# tractor_v2.net
KiCad netlist of a schematic drawn in EAGLE
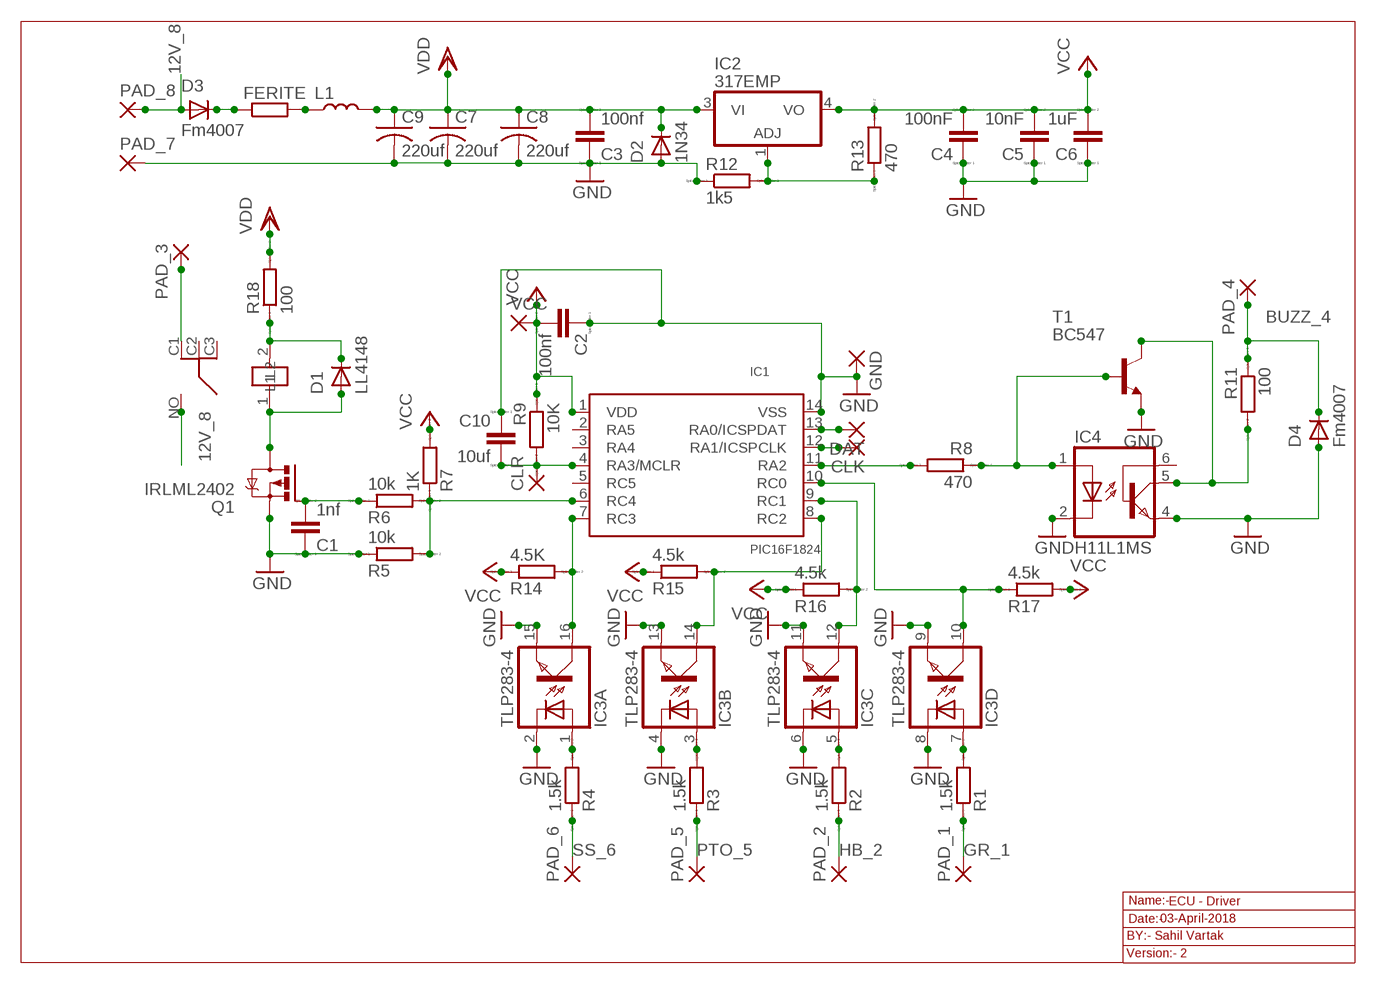
[diagram p0: schematic, sheet 1]

(export (version "E")
  (design (tool "Eeschema 10.0.6"))
  (components
    (comp (ref "C1")
      (value "1nf")
      (footprint "eagle-import:C0603")
      (libsource (lib "eagle-import") (part "CC0603"))
    )
    (comp (ref "C2")
      (value "100nf")
      (footprint "eagle-import:C0603")
      (libsource (lib "eagle-import") (part "CC0603"))
    )
    (comp (ref "C3")
      (value "100nf")
      (footprint "eagle-import:C0603")
      (libsource (lib "eagle-import") (part "CC0603"))
    )
    (comp (ref "C4")
      (value "100nF")
      (footprint "eagle-import:C0603")
      (libsource (lib "eagle-import") (part "CC0603"))
    )
    (comp (ref "C5")
      (value "10nF")
      (footprint "eagle-import:C0603")
      (libsource (lib "eagle-import") (part "CC0603"))
    )
    (comp (ref "C6")
      (value "1uF")
      (footprint "eagle-import:C0603")
      (libsource (lib "eagle-import") (part "CC0603"))
    )
    (comp (ref "C7")
      (value "220uf")
      (footprint "eagle-import:C025-025X050")
      (libsource (lib "eagle-import") (part "C-US025-025X050"))
    )
    (comp (ref "C8")
      (value "220uf")
      (footprint "eagle-import:C025-025X050")
      (libsource (lib "eagle-import") (part "C-US025-025X050"))
    )
    (comp (ref "C9")
      (value "220uf")
      (footprint "eagle-import:C025-025X050")
      (libsource (lib "eagle-import") (part "C-US025-025X050"))
    )
    (comp (ref "C10")
      (value "10uf")
      (footprint "eagle-import:C0603")
      (libsource (lib "eagle-import") (part "CC0603"))
    )
    (comp (ref "CLK")
      (value "1,6/0,8")
      (footprint "eagle-import:1,6_0,8")
      (libsource (lib "eagle-import") (part "1,6/0,8"))
    )
    (comp (ref "CLR")
      (value "1,6/0,8")
      (footprint "eagle-import:1,6_0,8")
      (libsource (lib "eagle-import") (part "1,6/0,8"))
    )
    (comp (ref "D1")
      (value "LL4148")
      (footprint "eagle-import:SMA-DO214AC")
      (libsource (lib "eagle-import") (part "GF1"))
    )
    (comp (ref "D2")
      (value "1N34")
      (footprint "eagle-import:SMA-DO214AC")
      (libsource (lib "eagle-import") (part "GF1"))
    )
    (comp (ref "D3")
      (value "Fm4007")
      (footprint "eagle-import:SMA-DO214AC")
      (libsource (lib "eagle-import") (part "GF1"))
    )
    (comp (ref "D4")
      (value "Fm4007")
      (footprint "eagle-import:SMA-DO214AC")
      (libsource (lib "eagle-import") (part "GF1"))
    )
    (comp (ref "DAT")
      (value "1,6/0,8")
      (footprint "eagle-import:1,6_0,8")
      (libsource (lib "eagle-import") (part "1,6/0,8"))
    )
    (comp (ref "FERITE")
      (value "R-EU_R0603")
      (footprint "eagle-import:R0603")
      (libsource (lib "eagle-import") (part "R-EU_R0603"))
    )
    (comp (ref "GND")
      (value "1,6/0,8")
      (footprint "eagle-import:1,6_0,8")
      (libsource (lib "eagle-import") (part "1,6/0,8"))
    )
    (comp (ref "IC1")
      (value "PIC16F1824")
      (footprint "eagle-import:SO-14")
      (libsource (lib "eagle-import") (part "PIC16F1824"))
    )
    (comp (ref "IC2")
      (value "317EMP")
      (footprint "eagle-import:SOT223")
      (libsource (lib "eagle-import") (part "317EMP"))
    )
    (comp (ref "IC3")
      (value "TLP283-4")
      (footprint "eagle-import:MINI-FLAT-16")
      (libsource (lib "eagle-import") (part "TLP283-4"))
    )
    (comp (ref "IC4")
      (value "H11L1MS")
      (footprint "eagle-import:DIL6-SMD")
      (libsource (lib "eagle-import") (part "H11LMS1"))
    )
    (comp (ref "K2")
      (value "RL703")
      (footprint "eagle-import:RL703")
      (libsource (lib "eagle-import") (part "RL703"))
    )
    (comp (ref "L1")
      (value "R-US_WSC2515")
      (footprint "eagle-import:WSC2515")
      (libsource (lib "eagle-import") (part "R-US_WSC2515"))
    )
    (comp (ref "PAD_1")
      (value "2,54/1,1")
      (footprint "eagle-import:2,54_1,1")
      (libsource (lib "eagle-import") (part "2,54/1,1"))
    )
    (comp (ref "PAD_2")
      (value "2,54/1,1")
      (footprint "eagle-import:2,54_1,1")
      (libsource (lib "eagle-import") (part "2,54/1,1"))
    )
    (comp (ref "PAD_3")
      (value "2,54/1,1")
      (footprint "eagle-import:2,54_1,1")
      (libsource (lib "eagle-import") (part "2,54/1,1"))
    )
    (comp (ref "PAD_4")
      (value "2,54/1,1")
      (footprint "eagle-import:2,54_1,1")
      (libsource (lib "eagle-import") (part "2,54/1,1"))
    )
    (comp (ref "PAD_5")
      (value "2,54/1,1")
      (footprint "eagle-import:2,54_1,1")
      (libsource (lib "eagle-import") (part "2,54/1,1"))
    )
    (comp (ref "PAD_6")
      (value "2,54/1,1")
      (footprint "eagle-import:2,54_1,1")
      (libsource (lib "eagle-import") (part "2,54/1,1"))
    )
    (comp (ref "PAD_7")
      (value "2,54/1,1")
      (footprint "eagle-import:2,54_1,1")
      (libsource (lib "eagle-import") (part "2,54/1,1"))
    )
    (comp (ref "PAD_8")
      (value "2,54/1,1")
      (footprint "eagle-import:2,54_1,1")
      (libsource (lib "eagle-import") (part "2,54/1,1"))
    )
    (comp (ref "Q1")
      (value "IRLML2402")
      (footprint "eagle-import:MICRO3")
      (libsource (lib "eagle-import") (part "IRLML5203"))
    )
    (comp (ref "R1")
      (value "1.5k")
      (footprint "eagle-import:R0603")
      (libsource (lib "eagle-import") (part "RR0603"))
    )
    (comp (ref "R2")
      (value "1.5k")
      (footprint "eagle-import:R0603")
      (libsource (lib "eagle-import") (part "RR0603"))
    )
    (comp (ref "R3")
      (value "1.5k")
      (footprint "eagle-import:R0603")
      (libsource (lib "eagle-import") (part "RR0603"))
    )
    (comp (ref "R4")
      (value "1.5k")
      (footprint "eagle-import:R0603")
      (libsource (lib "eagle-import") (part "RR0603"))
    )
    (comp (ref "R5")
      (value "10k")
      (footprint "eagle-import:R0603")
      (libsource (lib "eagle-import") (part "RR0603"))
    )
    (comp (ref "R6")
      (value "10k")
      (footprint "eagle-import:R0603")
      (libsource (lib "eagle-import") (part "RR0603"))
    )
    (comp (ref "R7")
      (value "1K")
      (footprint "eagle-import:R0603")
      (libsource (lib "eagle-import") (part "RR0603"))
    )
    (comp (ref "R8")
      (value "470")
      (footprint "eagle-import:R0603")
      (libsource (lib "eagle-import") (part "RR0603"))
    )
    (comp (ref "R9")
      (value "10K")
      (footprint "eagle-import:R0603")
      (libsource (lib "eagle-import") (part "RR0603"))
    )
    (comp (ref "R11")
      (value "100")
      (footprint "eagle-import:R0603")
      (libsource (lib "eagle-import") (part "RR0603"))
    )
    (comp (ref "R12")
      (value "1k5")
      (footprint "eagle-import:R0603")
      (libsource (lib "eagle-import") (part "RR0603"))
    )
    (comp (ref "R13")
      (value "470")
      (footprint "eagle-import:R0603")
      (libsource (lib "eagle-import") (part "RR0603"))
    )
    (comp (ref "R14")
      (value "4.5K")
      (footprint "eagle-import:R0603")
      (libsource (lib "eagle-import") (part "RR0603"))
    )
    (comp (ref "R15")
      (value "4.5k")
      (footprint "eagle-import:R0603")
      (libsource (lib "eagle-import") (part "RR0603"))
    )
    (comp (ref "R16")
      (value "4.5k")
      (footprint "eagle-import:R0603")
      (libsource (lib "eagle-import") (part "RR0603"))
    )
    (comp (ref "R17")
      (value "4.5k")
      (footprint "eagle-import:R0603")
      (libsource (lib "eagle-import") (part "RR0603"))
    )
    (comp (ref "R18")
      (value "100")
      (footprint "eagle-import:R0603")
      (libsource (lib "eagle-import") (part "RR0603"))
    )
    (comp (ref "T1")
      (value "BC547")
      (footprint "eagle-import:TO92")
      (libsource (lib "eagle-import") (part "BC547"))
    )
    (comp (ref "VCC")
      (value "1,6/0,8")
      (footprint "eagle-import:1,6_0,8")
      (libsource (lib "eagle-import") (part "1,6/0,8"))
    )
  )
  (nets
    (net (code "1") (name "/12V_8") (class "Default")
      (node (ref "D3") (pin "A") (pinfunction "A_A") (pintype "passive"))
      (node (ref "K2") (pin "NO") (pinfunction "NO_NO") (pintype "bidirectional"))
      (node (ref "PAD_8") (pin "1") (pinfunction "P_1") (pintype "passive"))
    )
    (net (code "2") (name "/BUZZ_4") (class "Default")
      (node (ref "D4") (pin "K") (pinfunction "C_K") (pintype "passive"))
      (node (ref "PAD_4") (pin "1") (pinfunction "P_1") (pintype "passive"))
      (node (ref "R11") (pin "1") (pinfunction "1_1") (pintype "passive"))
    )
    (net (code "3") (name "/GR_1") (class "Default")
      (node (ref "PAD_1") (pin "1") (pinfunction "P_1") (pintype "passive"))
      (node (ref "R1") (pin "1") (pinfunction "1_1") (pintype "passive"))
    )
    (net (code "4") (name "/HB_2") (class "Default")
      (node (ref "PAD_2") (pin "1") (pinfunction "P_1") (pintype "passive"))
      (node (ref "R2") (pin "1") (pinfunction "1_1") (pintype "passive"))
    )
    (net (code "5") (name "/PTO_5") (class "Default")
      (node (ref "PAD_5") (pin "1") (pinfunction "P_1") (pintype "passive"))
      (node (ref "R3") (pin "1") (pinfunction "1_1") (pintype "passive"))
    )
    (net (code "6") (name "/SS_6") (class "Default")
      (node (ref "PAD_6") (pin "1") (pinfunction "P_1") (pintype "passive"))
      (node (ref "R4") (pin "1") (pinfunction "1_1") (pintype "passive"))
    )
    (net (code "7") (name "GND") (class "Default")
      (node (ref "C1") (pin "1") (pinfunction "1_1") (pintype "passive"))
      (node (ref "C10") (pin "1") (pinfunction "1_1") (pintype "passive"))
      (node (ref "C2") (pin "1") (pinfunction "1_1") (pintype "passive"))
      (node (ref "C3") (pin "1") (pinfunction "1_1") (pintype "passive"))
      (node (ref "C4") (pin "1") (pinfunction "1_1") (pintype "passive"))
      (node (ref "C5") (pin "1") (pinfunction "1_1") (pintype "passive"))
      (node (ref "C6") (pin "1") (pinfunction "1_1") (pintype "passive"))
      (node (ref "C7") (pin "2") (pinfunction "2_2") (pintype "passive"))
      (node (ref "C8") (pin "2") (pinfunction "2_2") (pintype "passive"))
      (node (ref "C9") (pin "2") (pinfunction "2_2") (pintype "passive"))
      (node (ref "D2") (pin "A") (pinfunction "A_A") (pintype "passive"))
      (node (ref "D4") (pin "A") (pinfunction "A_A") (pintype "passive"))
      (node (ref "GND") (pin "1") (pinfunction "P_1") (pintype "passive"))
      (node (ref "IC1") (pin "14") (pinfunction "VSS_14") (pintype "bidirectional"))
      (node (ref "IC3") (pin "11") (pinfunction "EMIT_11") (pintype "passive"))
      (node (ref "IC3") (pin "13") (pinfunction "EMIT_13") (pintype "passive"))
      (node (ref "IC3") (pin "15") (pinfunction "EMIT_15") (pintype "passive"))
      (node (ref "IC3") (pin "2") (pinfunction "C_2") (pintype "passive"))
      (node (ref "IC3") (pin "4") (pinfunction "C_4") (pintype "passive"))
      (node (ref "IC3") (pin "6") (pinfunction "C_6") (pintype "passive"))
      (node (ref "IC3") (pin "8") (pinfunction "C_8") (pintype "passive"))
      (node (ref "IC3") (pin "9") (pinfunction "EMIT_9") (pintype "passive"))
      (node (ref "IC4") (pin "2") (pinfunction "C_2") (pintype "passive"))
      (node (ref "IC4") (pin "4") (pinfunction "EMI_4") (pintype "passive"))
      (node (ref "PAD_7") (pin "1") (pinfunction "P_1") (pintype "passive"))
      (node (ref "Q1") (pin "2") (pinfunction "S_2") (pintype "passive"))
      (node (ref "R12") (pin "1") (pinfunction "1_1") (pintype "passive"))
      (node (ref "R5") (pin "1") (pinfunction "1_1") (pintype "passive"))
      (node (ref "T1") (pin "1") (pinfunction "E_1") (pintype "passive"))
    )
    (net (code "8") (name "Net-(CLK-P)") (class "Default")
      (node (ref "CLK") (pin "1") (pinfunction "P_1") (pintype "passive"))
      (node (ref "IC1") (pin "12") (pinfunction "RA1/ICSPCLK_12") (pintype "bidirectional"))
    )
    (net (code "9") (name "Net-(CLR-P)") (class "Default")
      (node (ref "C10") (pin "2") (pinfunction "2_2") (pintype "passive"))
      (node (ref "CLR") (pin "1") (pinfunction "P_1") (pintype "passive"))
      (node (ref "IC1") (pin "4") (pinfunction "RA3/MCLR_4") (pintype "bidirectional"))
      (node (ref "R9") (pin "2") (pinfunction "2_2") (pintype "passive"))
    )
    (net (code "10") (name "Net-(D1-C)") (class "Default")
      (node (ref "D1") (pin "K") (pinfunction "C_K") (pintype "passive"))
      (node (ref "K2") (pin "2") (pinfunction "L1_2") (pintype "bidirectional"))
      (node (ref "R18") (pin "1") (pinfunction "1_1") (pintype "passive"))
    )
    (net (code "11") (name "Net-(D3-C)") (class "Default")
      (node (ref "D3") (pin "K") (pinfunction "C_K") (pintype "passive"))
      (node (ref "FERITE") (pin "1") (pinfunction "1_1") (pintype "passive"))
    )
    (net (code "12") (name "Net-(DAT-P)") (class "Default")
      (node (ref "DAT") (pin "1") (pinfunction "P_1") (pintype "passive"))
      (node (ref "IC1") (pin "13") (pinfunction "RA0/ICSPDAT_13") (pintype "bidirectional"))
    )
    (net (code "13") (name "Net-(FERITE-Pad2)") (class "Default")
      (node (ref "FERITE") (pin "2") (pinfunction "2_2") (pintype "passive"))
      (node (ref "L1") (pin "1") (pinfunction "1_1") (pintype "passive"))
    )
    (net (code "14") (name "Net-(IC1-RA2)") (class "Default")
      (node (ref "IC1") (pin "11") (pinfunction "RA2_11") (pintype "bidirectional"))
      (node (ref "R8") (pin "2") (pinfunction "2_2") (pintype "passive"))
    )
    (net (code "15") (name "Net-(IC1-RC0)") (class "Default")
      (node (ref "IC1") (pin "10") (pinfunction "RC0_10") (pintype "bidirectional"))
      (node (ref "IC3") (pin "10") (pinfunction "COL_10") (pintype "passive"))
      (node (ref "R17") (pin "1") (pinfunction "1_1") (pintype "passive"))
    )
    (net (code "16") (name "Net-(IC1-RC1)") (class "Default")
      (node (ref "IC1") (pin "9") (pinfunction "RC1_9") (pintype "bidirectional"))
      (node (ref "IC3") (pin "12") (pinfunction "COL_12") (pintype "passive"))
      (node (ref "R16") (pin "2") (pinfunction "2_2") (pintype "passive"))
    )
    (net (code "17") (name "Net-(IC1-RC2)") (class "Default")
      (node (ref "IC1") (pin "8") (pinfunction "RC2_8") (pintype "bidirectional"))
      (node (ref "IC3") (pin "14") (pinfunction "COL_14") (pintype "passive"))
      (node (ref "R15") (pin "2") (pinfunction "2_2") (pintype "passive"))
    )
    (net (code "18") (name "Net-(IC1-RC3)") (class "Default")
      (node (ref "IC1") (pin "7") (pinfunction "RC3_7") (pintype "bidirectional"))
      (node (ref "IC3") (pin "16") (pinfunction "COL_16") (pintype "passive"))
      (node (ref "R14") (pin "2") (pinfunction "2_2") (pintype "passive"))
    )
    (net (code "19") (name "Net-(IC1-RC4)") (class "Default")
      (node (ref "IC1") (pin "6") (pinfunction "RC4_6") (pintype "bidirectional"))
      (node (ref "R5") (pin "2") (pinfunction "2_2") (pintype "passive"))
      (node (ref "R6") (pin "2") (pinfunction "2_2") (pintype "passive"))
      (node (ref "R7") (pin "1") (pinfunction "1_1") (pintype "passive"))
    )
    (net (code "20") (name "Net-(IC2-ADJ)") (class "Default")
      (node (ref "IC2") (pin "1") (pinfunction "ADJ_1") (pintype "input"))
      (node (ref "R12") (pin "2") (pinfunction "2_2") (pintype "passive"))
      (node (ref "R13") (pin "1") (pinfunction "1_1") (pintype "passive"))
    )
    (net (code "21") (name "Net-(IC3A-A)") (class "Default")
      (node (ref "IC3") (pin "1") (pinfunction "A_1") (pintype "passive"))
      (node (ref "R4") (pin "2") (pinfunction "2_2") (pintype "passive"))
    )
    (net (code "22") (name "Net-(IC3B-A)") (class "Default")
      (node (ref "IC3") (pin "3") (pinfunction "A_3") (pintype "passive"))
      (node (ref "R3") (pin "2") (pinfunction "2_2") (pintype "passive"))
    )
    (net (code "23") (name "Net-(IC3C-A)") (class "Default")
      (node (ref "IC3") (pin "5") (pinfunction "A_5") (pintype "passive"))
      (node (ref "R2") (pin "2") (pinfunction "2_2") (pintype "passive"))
    )
    (net (code "24") (name "Net-(IC3D-A)") (class "Default")
      (node (ref "IC3") (pin "7") (pinfunction "A_7") (pintype "passive"))
      (node (ref "R1") (pin "2") (pinfunction "2_2") (pintype "passive"))
    )
    (net (code "25") (name "Net-(IC4-A)") (class "Default")
      (node (ref "IC4") (pin "1") (pinfunction "A_1") (pintype "passive"))
      (node (ref "R8") (pin "1") (pinfunction "1_1") (pintype "passive"))
      (node (ref "T1") (pin "2") (pinfunction "B_2") (pintype "passive"))
    )
    (net (code "26") (name "Net-(IC4-COL)") (class "Default")
      (node (ref "IC4") (pin "5") (pinfunction "COL_5") (pintype "passive"))
      (node (ref "R11") (pin "2") (pinfunction "2_2") (pintype "passive"))
      (node (ref "T1") (pin "3") (pinfunction "C_3") (pintype "passive"))
    )
    (net (code "27") (name "Net-(K2-L2)") (class "Default")
      (node (ref "D1") (pin "A") (pinfunction "A_A") (pintype "passive"))
      (node (ref "K2") (pin "1") (pinfunction "L2_1") (pintype "bidirectional"))
      (node (ref "Q1") (pin "3") (pinfunction "D_3") (pintype "passive"))
    )
    (net (code "28") (name "Net-(PAD_3-P)") (class "Default")
      (node (ref "K2") (pin "C1") (pinfunction "C1_C1") (pintype "bidirectional"))
      (node (ref "PAD_3") (pin "1") (pinfunction "P_1") (pintype "passive"))
    )
    (net (code "29") (name "Net-(Q1-G)") (class "Default")
      (node (ref "C1") (pin "2") (pinfunction "2_2") (pintype "passive"))
      (node (ref "Q1") (pin "1") (pinfunction "G_1") (pintype "passive"))
      (node (ref "R6") (pin "1") (pinfunction "1_1") (pintype "passive"))
    )
    (net (code "30") (name "VCC") (class "Default")
      (node (ref "C2") (pin "2") (pinfunction "2_2") (pintype "passive"))
      (node (ref "C4") (pin "2") (pinfunction "2_2") (pintype "passive"))
      (node (ref "C5") (pin "2") (pinfunction "2_2") (pintype "passive"))
      (node (ref "C6") (pin "2") (pinfunction "2_2") (pintype "passive"))
      (node (ref "IC1") (pin "1") (pinfunction "VDD_1") (pintype "bidirectional"))
      (node (ref "IC2") (pin "4") (pinfunction "VO_4") (pintype "passive"))
      (node (ref "R13") (pin "2") (pinfunction "2_2") (pintype "passive"))
      (node (ref "R14") (pin "1") (pinfunction "1_1") (pintype "passive"))
      (node (ref "R15") (pin "1") (pinfunction "1_1") (pintype "passive"))
      (node (ref "R16") (pin "1") (pinfunction "1_1") (pintype "passive"))
      (node (ref "R17") (pin "2") (pinfunction "2_2") (pintype "passive"))
      (node (ref "R7") (pin "2") (pinfunction "2_2") (pintype "passive"))
      (node (ref "R9") (pin "1") (pinfunction "1_1") (pintype "passive"))
      (node (ref "VCC") (pin "1") (pinfunction "P_1") (pintype "passive"))
    )
    (net (code "31") (name "VDD") (class "Default")
      (node (ref "C3") (pin "2") (pinfunction "2_2") (pintype "passive"))
      (node (ref "C7") (pin "1") (pinfunction "1_1") (pintype "passive"))
      (node (ref "C8") (pin "1") (pinfunction "1_1") (pintype "passive"))
      (node (ref "C9") (pin "1") (pinfunction "1_1") (pintype "passive"))
      (node (ref "D2") (pin "K") (pinfunction "C_K") (pintype "passive"))
      (node (ref "IC2") (pin "3") (pinfunction "VI_3") (pintype "input"))
      (node (ref "L1") (pin "2") (pinfunction "2_2") (pintype "passive"))
      (node (ref "R18") (pin "2") (pinfunction "2_2") (pintype "passive"))
    )
    (net (code "32") (name "unconnected-(IC1-RA4-Pad3)") (class "Default")
      (node (ref "IC1") (pin "3") (pinfunction "RA4_3") (pintype "bidirectional"))
    )
    (net (code "33") (name "unconnected-(IC1-RA5-Pad2)") (class "Default")
      (node (ref "IC1") (pin "2") (pinfunction "RA5_2") (pintype "bidirectional"))
    )
    (net (code "34") (name "unconnected-(IC1-RC5-Pad5)") (class "Default")
      (node (ref "IC1") (pin "5") (pinfunction "RC5_5") (pintype "bidirectional"))
    )
    (net (code "35") (name "unconnected-(IC4-BAS-Pad6)") (class "Default")
      (node (ref "IC4") (pin "6") (pinfunction "BAS_6") (pintype "passive"))
    )
    (net (code "36") (name "unconnected-(K2-PadC2)") (class "Default")
      (node (ref "K2") (pin "C2") (pinfunction "C2_C2") (pintype "bidirectional"))
    )
    (net (code "37") (name "unconnected-(K2-PadC3)") (class "Default")
      (node (ref "K2") (pin "C3") (pinfunction "C3_C3") (pintype "bidirectional"))
    )
  )
)
